# RPI_v5_PCM5122brd.net
KiCad netlist of a schematic drawn in EAGLE
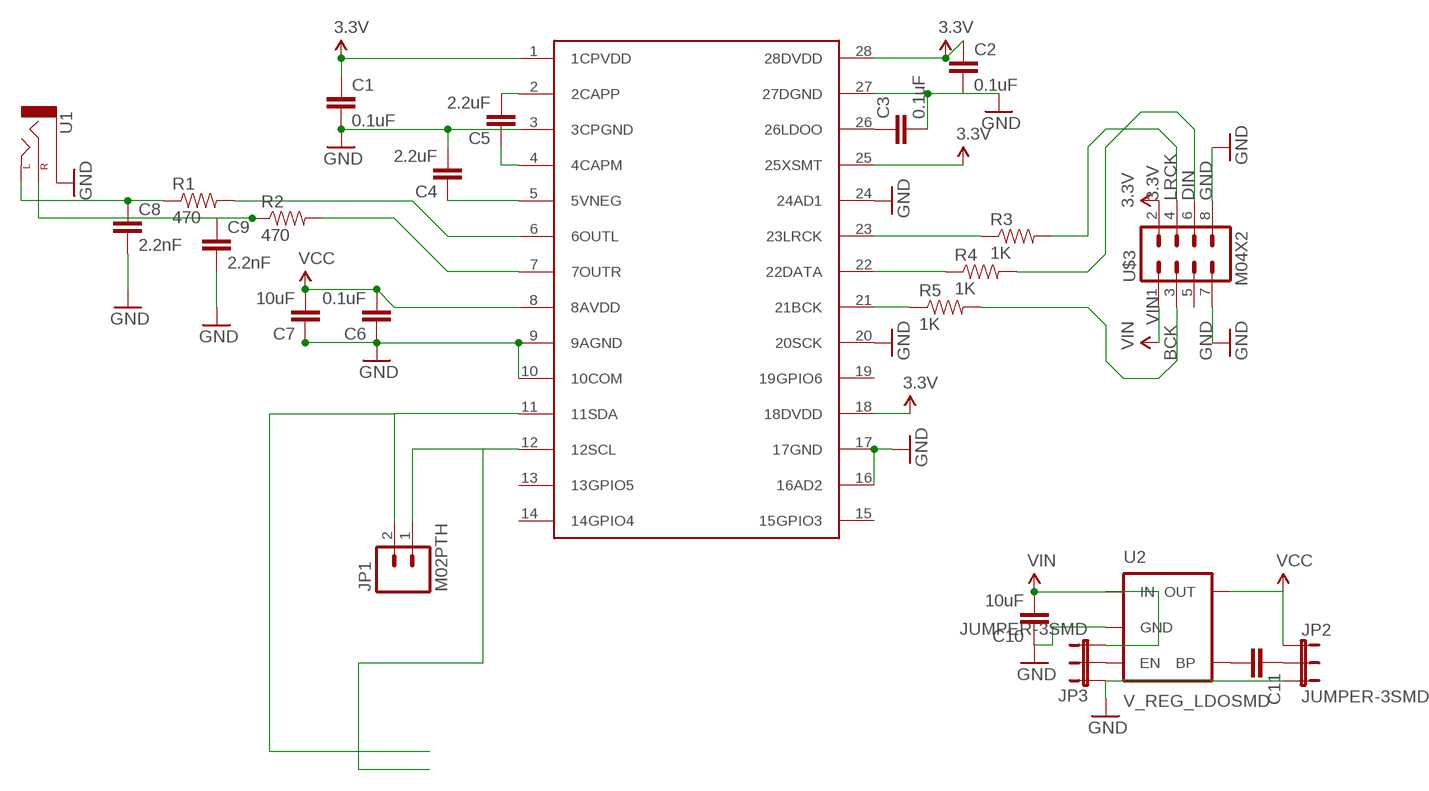
[diagram p0: schematic, sheet 1]

(export (version "E")
  (design (tool "Eeschema 10.0.6"))
  (components
    (comp (ref "C1")
      (value "0.1uF")
      (footprint "eagle-import:0805")
      (libsource (lib "eagle-import") (part "CAP0805"))
    )
    (comp (ref "C2")
      (value "0.1uF")
      (footprint "eagle-import:0805")
      (libsource (lib "eagle-import") (part "CAP0805"))
    )
    (comp (ref "C3")
      (value "0.1uF")
      (footprint "eagle-import:0805")
      (libsource (lib "eagle-import") (part "CAP0805"))
    )
    (comp (ref "C4")
      (value "2.2uF")
      (footprint "eagle-import:0805")
      (libsource (lib "eagle-import") (part "CAP0805"))
    )
    (comp (ref "C5")
      (value "2.2uF")
      (footprint "eagle-import:0805")
      (libsource (lib "eagle-import") (part "CAP0805"))
    )
    (comp (ref "C6")
      (value "0.1uF")
      (footprint "eagle-import:0805")
      (libsource (lib "eagle-import") (part "CAP0805"))
    )
    (comp (ref "C7")
      (value "10uF")
      (footprint "eagle-import:0805")
      (libsource (lib "eagle-import") (part "CAP0805"))
    )
    (comp (ref "C8")
      (value "2.2nF")
      (footprint "eagle-import:CAP-PTH-5MM")
      (libsource (lib "eagle-import") (part "CAPPTH1"))
    )
    (comp (ref "C9")
      (value "2.2nF")
      (footprint "eagle-import:CAP-PTH-5MM")
      (libsource (lib "eagle-import") (part "CAPPTH1"))
    )
    (comp (ref "C10")
      (value "10uF")
      (footprint "eagle-import:0805")
      (libsource (lib "eagle-import") (part "CAP0805"))
    )
    (comp (ref "C11")
      (value "CAP0805")
      (footprint "eagle-import:0805")
      (libsource (lib "eagle-import") (part "CAP0805"))
    )
    (comp (ref "JP1")
      (value "M02PTH")
      (footprint "eagle-import:1X02")
      (libsource (lib "eagle-import") (part "M02PTH"))
    )
    (comp (ref "JP2")
      (value "JUMPER-3SMD")
      (footprint "eagle-import:SJ_3")
      (libsource (lib "eagle-import") (part "JUMPER-3SMD"))
    )
    (comp (ref "JP3")
      (value "JUMPER-3SMD")
      (footprint "eagle-import:SJ_3")
      (libsource (lib "eagle-import") (part "JUMPER-3SMD"))
    )
    (comp (ref "R1")
      (value "470")
      (footprint "eagle-import:AXIAL-0.4")
      (libsource (lib "eagle-import") (part "RESISTORPTH-1/4W"))
    )
    (comp (ref "R2")
      (value "470")
      (footprint "eagle-import:AXIAL-0.4")
      (libsource (lib "eagle-import") (part "RESISTORPTH-1/4W"))
    )
    (comp (ref "R3")
      (value "1K")
      (footprint "eagle-import:0805")
      (libsource (lib "eagle-import") (part "RESISTOR0805-RES"))
    )
    (comp (ref "R4")
      (value "1K")
      (footprint "eagle-import:0805")
      (libsource (lib "eagle-import") (part "RESISTOR0805-RES"))
    )
    (comp (ref "R5")
      (value "1K")
      (footprint "eagle-import:0805")
      (libsource (lib "eagle-import") (part "RESISTOR0805-RES"))
    )
    (comp (ref "U$3")
      (value "M04X2")
      (footprint "eagle-import:2X4")
      (libsource (lib "eagle-import") (part "M04X2"))
    )
    (comp (ref "U$5")
      (value "PCM5122")
      (footprint "eagle-import:TSSOP28")
      (libsource (lib "eagle-import") (part "PCM5122"))
    )
    (comp (ref "U1")
      (value "AUDIO-JACKPTH")
      (footprint "eagle-import:AUDIO-JACK")
      (libsource (lib "eagle-import") (part "AUDIO-JACKPTH"))
    )
    (comp (ref "U2")
      (value "V_REG_LDOSMD")
      (footprint "eagle-import:SOT23-5")
      (libsource (lib "eagle-import") (part "V_REG_LDOSMD"))
    )
  )
  (nets
    (net (code "1") (name "/BCK") (class "Default")
      (node (ref "R5") (pin "2") (pinfunction "2_2") (pintype "passive"))
      (node (ref "U$3") (pin "3") (pinfunction "3_3") (pintype "passive"))
    )
    (net (code "2") (name "/DIN") (class "Default")
      (node (ref "R4") (pin "2") (pinfunction "2_2") (pintype "passive"))
      (node (ref "U$3") (pin "6") (pinfunction "6_6") (pintype "passive"))
    )
    (net (code "3") (name "/LRCK") (class "Default")
      (node (ref "R3") (pin "2") (pinfunction "2_2") (pintype "passive"))
      (node (ref "U$3") (pin "4") (pinfunction "4_4") (pintype "passive"))
    )
    (net (code "4") (name "3.3V") (class "Default")
      (node (ref "C1") (pin "1") (pinfunction "1_1") (pintype "passive"))
      (node (ref "C2") (pin "1") (pinfunction "1_1") (pintype "passive"))
      (node (ref "U$3") (pin "2") (pinfunction "2_2") (pintype "passive"))
      (node (ref "U$5") (pin "1") (pinfunction "1CPVDD_1") (pintype "bidirectional"))
      (node (ref "U$5") (pin "18") (pinfunction "18DVDD_18") (pintype "bidirectional"))
      (node (ref "U$5") (pin "25") (pinfunction "25XSMT_25") (pintype "bidirectional"))
      (node (ref "U$5") (pin "28") (pinfunction "28DVDD_28") (pintype "bidirectional"))
    )
    (net (code "5") (name "GND") (class "Default")
      (node (ref "C1") (pin "2") (pinfunction "2_2") (pintype "passive"))
      (node (ref "C10") (pin "1") (pinfunction "1_1") (pintype "passive"))
      (node (ref "C2") (pin "2") (pinfunction "2_2") (pintype "passive"))
      (node (ref "C3") (pin "2") (pinfunction "2_2") (pintype "passive"))
      (node (ref "C4") (pin "2") (pinfunction "2_2") (pintype "passive"))
      (node (ref "C6") (pin "1") (pinfunction "1_1") (pintype "passive"))
      (node (ref "C7") (pin "1") (pinfunction "1_1") (pintype "passive"))
      (node (ref "C8") (pin "2") (pinfunction "2_2") (pintype "passive"))
      (node (ref "C9") (pin "2") (pinfunction "2_2") (pintype "passive"))
      (node (ref "JP2") (pin "3") (pinfunction "3_3") (pintype "passive"))
      (node (ref "JP3") (pin "1") (pinfunction "1_1") (pintype "passive"))
      (node (ref "U$3") (pin "7") (pinfunction "7_7") (pintype "passive"))
      (node (ref "U$3") (pin "8") (pinfunction "8_8") (pintype "passive"))
      (node (ref "U$5") (pin "10") (pinfunction "10COM_10") (pintype "bidirectional"))
      (node (ref "U$5") (pin "16") (pinfunction "16AD2_16") (pintype "bidirectional"))
      (node (ref "U$5") (pin "17") (pinfunction "17GND_17") (pintype "bidirectional"))
      (node (ref "U$5") (pin "20") (pinfunction "20SCK_20") (pintype "bidirectional"))
      (node (ref "U$5") (pin "24") (pinfunction "24AD1_24") (pintype "bidirectional"))
      (node (ref "U$5") (pin "27") (pinfunction "27DGND_27") (pintype "bidirectional"))
      (node (ref "U$5") (pin "3") (pinfunction "3CPGND_3") (pintype "bidirectional"))
      (node (ref "U$5") (pin "9") (pinfunction "9AGND_9") (pintype "bidirectional"))
      (node (ref "U1") (pin "SLEEVE") (pinfunction "SLEEVE_SLEEVE") (pintype "bidirectional"))
      (node (ref "U2") (pin "2") (pinfunction "GND_2") (pintype "input"))
    )
    (net (code "6") (name "Net-(C11-Pad1)") (class "Default")
      (node (ref "C11") (pin "1") (pinfunction "1_1") (pintype "passive"))
      (node (ref "JP2") (pin "2") (pinfunction "2_2") (pintype "passive"))
    )
    (net (code "7") (name "Net-(R1-1)") (class "Default")
      (node (ref "C8") (pin "1") (pinfunction "1_1") (pintype "passive"))
      (node (ref "R1") (pin "P$1") (pinfunction "1_P$1") (pintype "passive"))
      (node (ref "U1") (pin "TIP") (pinfunction "LEFT_TIP") (pintype "bidirectional"))
    )
    (net (code "8") (name "Net-(R1-2)") (class "Default")
      (node (ref "R1") (pin "P$2") (pinfunction "2_P$2") (pintype "passive"))
      (node (ref "U$5") (pin "6") (pinfunction "6OUTL_6") (pintype "bidirectional"))
    )
    (net (code "9") (name "Net-(R2-1)") (class "Default")
      (node (ref "C9") (pin "1") (pinfunction "1_1") (pintype "passive"))
      (node (ref "R2") (pin "P$1") (pinfunction "1_P$1") (pintype "passive"))
      (node (ref "U1") (pin "RING") (pinfunction "RIGHT_RING") (pintype "bidirectional"))
    )
    (net (code "10") (name "Net-(R2-2)") (class "Default")
      (node (ref "R2") (pin "P$2") (pinfunction "2_P$2") (pintype "passive"))
      (node (ref "U$5") (pin "7") (pinfunction "7OUTR_7") (pintype "bidirectional"))
    )
    (net (code "11") (name "Net-(U$5-2CAPP)") (class "Default")
      (node (ref "C5") (pin "2") (pinfunction "2_2") (pintype "passive"))
      (node (ref "U$5") (pin "2") (pinfunction "2CAPP_2") (pintype "bidirectional"))
    )
    (net (code "12") (name "Net-(U$5-4CAPM)") (class "Default")
      (node (ref "C5") (pin "1") (pinfunction "1_1") (pintype "passive"))
      (node (ref "U$5") (pin "4") (pinfunction "4CAPM_4") (pintype "bidirectional"))
    )
    (net (code "13") (name "Net-(U$5-5VNEG)") (class "Default")
      (node (ref "C4") (pin "1") (pinfunction "1_1") (pintype "passive"))
      (node (ref "U$5") (pin "5") (pinfunction "5VNEG_5") (pintype "bidirectional"))
    )
    (net (code "14") (name "Net-(U$5-11SDA)") (class "Default")
      (node (ref "JP1") (pin "2") (pinfunction "2_2") (pintype "passive"))
      (node (ref "U$5") (pin "11") (pinfunction "11SDA_11") (pintype "bidirectional"))
    )
    (net (code "15") (name "Net-(U$5-12SCL)") (class "Default")
      (node (ref "JP1") (pin "1") (pinfunction "1_1") (pintype "passive"))
      (node (ref "U$5") (pin "12") (pinfunction "12SCL_12") (pintype "bidirectional"))
    )
    (net (code "16") (name "Net-(U$5-21BCK)") (class "Default")
      (node (ref "R5") (pin "1") (pinfunction "1_1") (pintype "passive"))
      (node (ref "U$5") (pin "21") (pinfunction "21BCK_21") (pintype "bidirectional"))
    )
    (net (code "17") (name "Net-(U$5-22DATA)") (class "Default")
      (node (ref "R4") (pin "1") (pinfunction "1_1") (pintype "passive"))
      (node (ref "U$5") (pin "22") (pinfunction "22DATA_22") (pintype "bidirectional"))
    )
    (net (code "18") (name "Net-(U$5-23LRCK)") (class "Default")
      (node (ref "R3") (pin "1") (pinfunction "1_1") (pintype "passive"))
      (node (ref "U$5") (pin "23") (pinfunction "23LRCK_23") (pintype "bidirectional"))
    )
    (net (code "19") (name "Net-(U$5-26LDOO)") (class "Default")
      (node (ref "C3") (pin "1") (pinfunction "1_1") (pintype "passive"))
      (node (ref "U$5") (pin "26") (pinfunction "26LDOO_26") (pintype "bidirectional"))
    )
    (net (code "20") (name "Net-(U2-BP)") (class "Default")
      (node (ref "C11") (pin "2") (pinfunction "2_2") (pintype "passive"))
      (node (ref "U2") (pin "4") (pinfunction "BP_4") (pintype "input"))
    )
    (net (code "21") (name "Net-(U2-EN)") (class "Default")
      (node (ref "JP3") (pin "2") (pinfunction "2_2") (pintype "passive"))
      (node (ref "U2") (pin "3") (pinfunction "EN_3") (pintype "input"))
    )
    (net (code "22") (name "VCC") (class "Default")
      (node (ref "C6") (pin "2") (pinfunction "2_2") (pintype "passive"))
      (node (ref "C7") (pin "2") (pinfunction "2_2") (pintype "passive"))
      (node (ref "JP2") (pin "1") (pinfunction "1_1") (pintype "passive"))
      (node (ref "U$5") (pin "8") (pinfunction "8AVDD_8") (pintype "bidirectional"))
      (node (ref "U2") (pin "5") (pinfunction "OUT_5") (pintype "passive"))
    )
    (net (code "23") (name "VIN") (class "Default")
      (node (ref "C10") (pin "2") (pinfunction "2_2") (pintype "passive"))
      (node (ref "JP3") (pin "3") (pinfunction "3_3") (pintype "passive"))
      (node (ref "U$3") (pin "1") (pinfunction "1_1") (pintype "passive"))
      (node (ref "U2") (pin "1") (pinfunction "IN_1") (pintype "input"))
    )
    (net (code "24") (name "unconnected-(U$3-Pad5)") (class "Default")
      (node (ref "U$3") (pin "5") (pinfunction "5_5") (pintype "passive"))
    )
    (net (code "25") (name "unconnected-(U$5-13GPIO5-Pad13)") (class "Default")
      (node (ref "U$5") (pin "13") (pinfunction "13GPIO5_13") (pintype "bidirectional"))
    )
    (net (code "26") (name "unconnected-(U$5-14GPIO4-Pad14)") (class "Default")
      (node (ref "U$5") (pin "14") (pinfunction "14GPIO4_14") (pintype "bidirectional"))
    )
    (net (code "27") (name "unconnected-(U$5-15GPIO3-Pad15)") (class "Default")
      (node (ref "U$5") (pin "15") (pinfunction "15GPIO3_15") (pintype "bidirectional"))
    )
    (net (code "28") (name "unconnected-(U$5-19GPIO6-Pad19)") (class "Default")
      (node (ref "U$5") (pin "19") (pinfunction "19GPIO6_19") (pintype "bidirectional"))
    )
  )
)
